# DDS_Tone_Shield.net
KiCad netlist of a schematic drawn in EAGLE
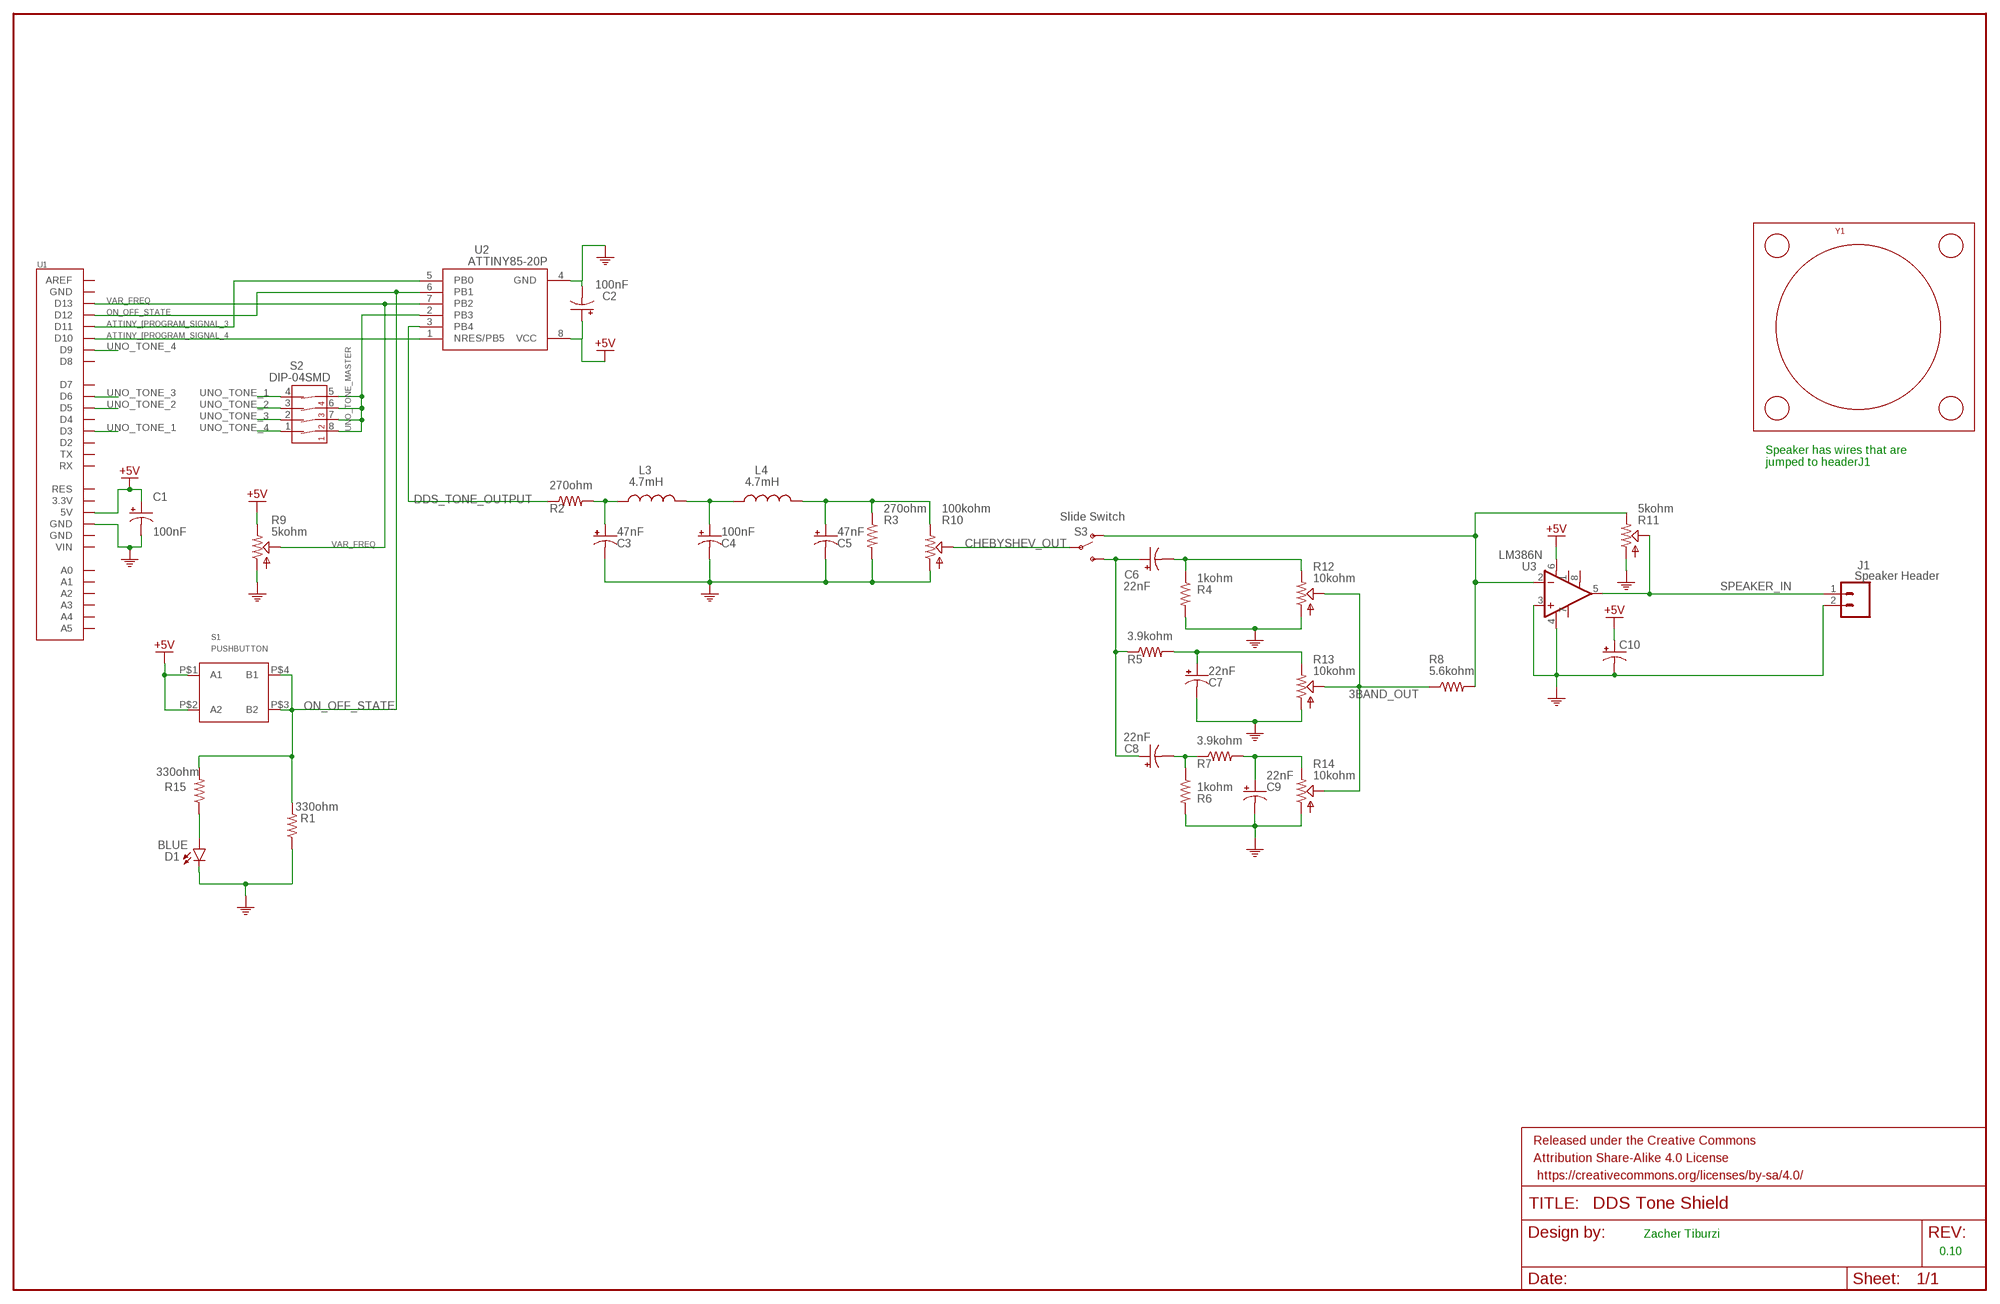
[diagram p0: schematic, sheet 1]

(export (version "E")
  (design (tool "Eeschema 10.0.6"))
  (components
    (comp (ref "C1")
      (value "100nF")
      (footprint "eagle-import:EIA3216")
      (libsource (lib "eagle-import") (part "CAP_POL1206"))
    )
    (comp (ref "C2")
      (value "100nF")
      (footprint "eagle-import:EIA3216")
      (libsource (lib "eagle-import") (part "CAP_POL1206"))
    )
    (comp (ref "C3")
      (value "47nF")
      (footprint "eagle-import:EIA3216")
      (libsource (lib "eagle-import") (part "CAP_POL1206"))
    )
    (comp (ref "C4")
      (value "100nF")
      (footprint "eagle-import:EIA3216")
      (libsource (lib "eagle-import") (part "CAP_POL1206"))
    )
    (comp (ref "C5")
      (value "47nF")
      (footprint "eagle-import:EIA3216")
      (libsource (lib "eagle-import") (part "CAP_POL1206"))
    )
    (comp (ref "C6")
      (value "22nF")
      (footprint "eagle-import:EIA3216")
      (libsource (lib "eagle-import") (part "CAP_POL1206"))
    )
    (comp (ref "C7")
      (value "22nF")
      (footprint "eagle-import:EIA3216")
      (libsource (lib "eagle-import") (part "CAP_POL1206"))
    )
    (comp (ref "C8")
      (value "22nF")
      (footprint "eagle-import:EIA3216")
      (libsource (lib "eagle-import") (part "CAP_POL1206"))
    )
    (comp (ref "C9")
      (value "22nF")
      (footprint "eagle-import:EIA3216")
      (libsource (lib "eagle-import") (part "CAP_POL1206"))
    )
    (comp (ref "C10")
      (value "CAP_POL1206")
      (footprint "eagle-import:EIA3216")
      (libsource (lib "eagle-import") (part "CAP_POL1206"))
    )
    (comp (ref "D1")
      (value "BLUE")
      (footprint "eagle-import:LED-1206")
      (libsource (lib "eagle-import") (part "LED-BLUE1206"))
    )
    (comp (ref "FRAME2")
      (value "FRAME-LEDGER")
      (footprint "eagle-import:CREATIVE_COMMONS")
      (libsource (lib "eagle-import") (part "FRAME-LEDGER"))
    )
    (comp (ref "J1")
      (value "Speaker Header")
      (footprint "eagle-import:1X02")
      (libsource (lib "eagle-import") (part "CONN_02"))
    )
    (comp (ref "L3")
      (value "4.7mH")
      (footprint "eagle-import:SDR0503-472JL")
      (libsource (lib "eagle-import") (part "INDUCTOR_"))
    )
    (comp (ref "L4")
      (value "4.7mH")
      (footprint "eagle-import:SDR0503-472JL")
      (libsource (lib "eagle-import") (part "INDUCTOR_"))
    )
    (comp (ref "R1")
      (value "330ohm")
      (footprint "eagle-import:1206")
      (libsource (lib "eagle-import") (part "RESISTOR1206"))
    )
    (comp (ref "R2")
      (value "270ohm")
      (footprint "eagle-import:1206")
      (libsource (lib "eagle-import") (part "RESISTOR1206"))
    )
    (comp (ref "R3")
      (value "270ohm")
      (footprint "eagle-import:1206")
      (libsource (lib "eagle-import") (part "RESISTOR1206"))
    )
    (comp (ref "R4")
      (value "1kohm")
      (footprint "eagle-import:1206")
      (libsource (lib "eagle-import") (part "RESISTOR1206"))
    )
    (comp (ref "R5")
      (value "3.9kohm")
      (footprint "eagle-import:1206")
      (libsource (lib "eagle-import") (part "RESISTOR1206"))
    )
    (comp (ref "R6")
      (value "1kohm")
      (footprint "eagle-import:1206")
      (libsource (lib "eagle-import") (part "RESISTOR1206"))
    )
    (comp (ref "R7")
      (value "3.9kohm")
      (footprint "eagle-import:1206")
      (libsource (lib "eagle-import") (part "RESISTOR1206"))
    )
    (comp (ref "R8")
      (value "5.6kohm")
      (footprint "eagle-import:1206")
      (libsource (lib "eagle-import") (part "RESISTOR1206"))
    )
    (comp (ref "R9")
      (value "5kohm")
      (footprint "eagle-import:RK09K_RK09D_SERIES")
      (libsource (lib "eagle-import") (part "POT1"))
    )
    (comp (ref "R10")
      (value "100kohm")
      (footprint "eagle-import:5150500311")
      (libsource (lib "eagle-import") (part "POT2"))
    )
    (comp (ref "R11")
      (value "5kohm")
      (footprint "eagle-import:RK09K_RK09D_SERIES")
      (libsource (lib "eagle-import") (part "POT1"))
    )
    (comp (ref "R12")
      (value "10kohm")
      (footprint "eagle-import:RK09K_RK09D_SERIES")
      (libsource (lib "eagle-import") (part "POT1"))
    )
    (comp (ref "R13")
      (value "10kohm")
      (footprint "eagle-import:RK09K_RK09D_SERIES")
      (libsource (lib "eagle-import") (part "POT1"))
    )
    (comp (ref "R14")
      (value "10kohm")
      (footprint "eagle-import:RK09K_RK09D_SERIES")
      (libsource (lib "eagle-import") (part "POT1"))
    )
    (comp (ref "R15")
      (value "330ohm")
      (footprint "eagle-import:1206")
      (libsource (lib "eagle-import") (part "RESISTOR1206"))
    )
    (comp (ref "S1")
      (value "PUSHBUTTON")
      (footprint "eagle-import:3CSH9_MEC_PUSHBUTTON")
      (libsource (lib "eagle-import") (part "PUSHBUTTON"))
    )
    (comp (ref "S2")
      (value "DIP-04SMD")
      (footprint "eagle-import:DIPSWITCH-04-SMD")
      (libsource (lib "eagle-import") (part "DIP-04SMD"))
    )
    (comp (ref "S3")
      (value "Slide Switch")
      (footprint "eagle-import:JS102011SAQN")
      (libsource (lib "eagle-import") (part "SWITCH-SPDT"))
    )
    (comp (ref "U1")
      (value "ARDUINO_SHIELD")
      (footprint "eagle-import:DUEMILANOVE_SHIELD")
      (libsource (lib "eagle-import") (part "ARDUINO_SHIELD"))
    )
    (comp (ref "U2")
      (value "ATTINY85-20P")
      (footprint "eagle-import:PDIP08_300MIL")
      (libsource (lib "eagle-import") (part "ATTINY85P-20"))
    )
    (comp (ref "U3")
      (value "LM386N")
      (footprint "eagle-import:DIP08")
      (libsource (lib "eagle-import") (part "LM386"))
    )
    (comp (ref "Y1")
      (value "SPEAKER")
      (footprint "eagle-import:CSS-40408N")
      (libsource (lib "eagle-import") (part "SPEAKER"))
    )
  )
  (nets
    (net (code "1") (name "+5V") (class "Default")
      (node (ref "C1") (pin "A") (pinfunction "+_A") (pintype "passive"))
      (node (ref "C10") (pin "A") (pinfunction "+_A") (pintype "passive"))
      (node (ref "C2") (pin "A") (pinfunction "+_A") (pintype "passive"))
      (node (ref "R9") (pin "P$3") (pinfunction "E_P$3") (pintype "passive"))
      (node (ref "S1") (pin "P$1") (pinfunction "A1_P$1") (pintype "bidirectional"))
      (node (ref "S1") (pin "P$2") (pinfunction "A2_P$2") (pintype "bidirectional"))
      (node (ref "U1") (pin "5V") (pinfunction "5V_5V") (pintype "bidirectional"))
      (node (ref "U2") (pin "8") (pinfunction "VCC_8") (pintype "power_in"))
      (node (ref "U3") (pin "6") (pinfunction "V+_6") (pintype "power_in"))
    )
    (net (code "2") (name "/3BAND_OUT") (class "Default")
      (node (ref "R12") (pin "P$2") (pinfunction "S_P$2") (pintype "passive"))
      (node (ref "R13") (pin "P$2") (pinfunction "S_P$2") (pintype "passive"))
      (node (ref "R14") (pin "P$2") (pinfunction "S_P$2") (pintype "passive"))
      (node (ref "R8") (pin "1") (pinfunction "1_1") (pintype "passive"))
    )
    (net (code "3") (name "/ATTINY_[PROGRAM_SIGNAL_3") (class "Default")
      (node (ref "U1") (pin "D11") (pinfunction "D11_D11") (pintype "bidirectional"))
      (node (ref "U2") (pin "5") (pinfunction "PB0_5") (pintype "bidirectional"))
    )
    (net (code "4") (name "/ATTINY_[PROGRAM_SIGNAL_4") (class "Default")
      (node (ref "U1") (pin "D10") (pinfunction "D10_D10") (pintype "bidirectional"))
      (node (ref "U2") (pin "1") (pinfunction "NRES/PB5_1") (pintype "bidirectional"))
    )
    (net (code "5") (name "/CHEBYSHEV_OUT") (class "Default")
      (node (ref "R10") (pin "P$20") (pinfunction "S_P$20") (pintype "passive"))
      (node (ref "S3") (pin "P$3") (pinfunction "P_P$3") (pintype "passive"))
    )
    (net (code "6") (name "/DDS_TONE_OUTPUT") (class "Default")
      (node (ref "R2") (pin "1") (pinfunction "1_1") (pintype "passive"))
      (node (ref "U2") (pin "3") (pinfunction "PB4_3") (pintype "bidirectional"))
    )
    (net (code "7") (name "/ON_OFF_STATE") (class "Default")
      (node (ref "R1") (pin "2") (pinfunction "2_2") (pintype "passive"))
      (node (ref "R15") (pin "2") (pinfunction "2_2") (pintype "passive"))
      (node (ref "S1") (pin "P$3") (pinfunction "B2_P$3") (pintype "bidirectional"))
      (node (ref "S1") (pin "P$4") (pinfunction "B1_P$4") (pintype "bidirectional"))
      (node (ref "U1") (pin "D12") (pinfunction "D12_D12") (pintype "bidirectional"))
      (node (ref "U2") (pin "6") (pinfunction "PB1_6") (pintype "bidirectional"))
    )
    (net (code "8") (name "/SPEAKER_IN") (class "Default")
      (node (ref "J1") (pin "1") (pinfunction "1_1") (pintype "passive"))
      (node (ref "R11") (pin "P$2") (pinfunction "S_P$2") (pintype "passive"))
      (node (ref "U3") (pin "5") (pinfunction "OUT_5") (pintype "output"))
    )
    (net (code "9") (name "/UNO_TONE_1") (class "Default")
      (node (ref "S2") (pin "4") (pinfunction "4A_4") (pintype "bidirectional"))
      (node (ref "U1") (pin "D3") (pinfunction "D3_D3") (pintype "bidirectional"))
    )
    (net (code "10") (name "/UNO_TONE_2") (class "Default")
      (node (ref "S2") (pin "3") (pinfunction "3A_3") (pintype "bidirectional"))
      (node (ref "U1") (pin "D5") (pinfunction "D5_D5") (pintype "bidirectional"))
    )
    (net (code "11") (name "/UNO_TONE_3") (class "Default")
      (node (ref "S2") (pin "2") (pinfunction "2A_2") (pintype "bidirectional"))
      (node (ref "U1") (pin "D6") (pinfunction "D6_D6") (pintype "bidirectional"))
    )
    (net (code "12") (name "/UNO_TONE_4") (class "Default")
      (node (ref "S2") (pin "1") (pinfunction "1A_1") (pintype "bidirectional"))
      (node (ref "U1") (pin "D9") (pinfunction "D9_D9") (pintype "bidirectional"))
    )
    (net (code "13") (name "/UNO_TONE_MASTER") (class "Default")
      (node (ref "S2") (pin "5") (pinfunction "4B_5") (pintype "bidirectional"))
      (node (ref "S2") (pin "6") (pinfunction "3B_6") (pintype "bidirectional"))
      (node (ref "S2") (pin "7") (pinfunction "2B_7") (pintype "bidirectional"))
      (node (ref "S2") (pin "8") (pinfunction "1B_8") (pintype "bidirectional"))
      (node (ref "U2") (pin "2") (pinfunction "PB3_2") (pintype "bidirectional"))
    )
    (net (code "14") (name "/VAR_FREQ") (class "Default")
      (node (ref "R9") (pin "P$2") (pinfunction "S_P$2") (pintype "passive"))
      (node (ref "U1") (pin "D13") (pinfunction "D13_D13") (pintype "bidirectional"))
      (node (ref "U2") (pin "7") (pinfunction "PB2_7") (pintype "bidirectional"))
    )
    (net (code "15") (name "GND_US") (class "Default")
      (node (ref "C1") (pin "C") (pinfunction "-_C") (pintype "passive"))
      (node (ref "C10") (pin "C") (pinfunction "-_C") (pintype "passive"))
      (node (ref "C2") (pin "C") (pinfunction "-_C") (pintype "passive"))
      (node (ref "C3") (pin "C") (pinfunction "-_C") (pintype "passive"))
      (node (ref "C4") (pin "C") (pinfunction "-_C") (pintype "passive"))
      (node (ref "C5") (pin "C") (pinfunction "-_C") (pintype "passive"))
      (node (ref "C7") (pin "C") (pinfunction "-_C") (pintype "passive"))
      (node (ref "C9") (pin "C") (pinfunction "-_C") (pintype "passive"))
      (node (ref "D1") (pin "C") (pinfunction "C_C") (pintype "passive"))
      (node (ref "J1") (pin "2") (pinfunction "2_2") (pintype "passive"))
      (node (ref "R1") (pin "1") (pinfunction "1_1") (pintype "passive"))
      (node (ref "R10") (pin "P$10") (pinfunction "A_P$10") (pintype "passive"))
      (node (ref "R11") (pin "P$1") (pinfunction "A_P$1") (pintype "passive"))
      (node (ref "R12") (pin "P$1") (pinfunction "A_P$1") (pintype "passive"))
      (node (ref "R13") (pin "P$1") (pinfunction "A_P$1") (pintype "passive"))
      (node (ref "R14") (pin "P$1") (pinfunction "A_P$1") (pintype "passive"))
      (node (ref "R3") (pin "2") (pinfunction "2_2") (pintype "passive"))
      (node (ref "R4") (pin "2") (pinfunction "2_2") (pintype "passive"))
      (node (ref "R6") (pin "2") (pinfunction "2_2") (pintype "passive"))
      (node (ref "R9") (pin "P$1") (pinfunction "A_P$1") (pintype "passive"))
      (node (ref "U1") (pin "GND@1") (pinfunction "GND_GND@1") (pintype "bidirectional"))
      (node (ref "U2") (pin "4") (pinfunction "GND_4") (pintype "power_in"))
      (node (ref "U3") (pin "3") (pinfunction "+IN_3") (pintype "input"))
      (node (ref "U3") (pin "4") (pinfunction "V-_4") (pintype "power_in"))
    )
    (net (code "16") (name "Net-(C3-+)") (class "Default")
      (node (ref "C3") (pin "A") (pinfunction "+_A") (pintype "passive"))
      (node (ref "L3") (pin "P$1") (pinfunction "1_P$1") (pintype "passive"))
      (node (ref "R2") (pin "2") (pinfunction "2_2") (pintype "passive"))
    )
    (net (code "17") (name "Net-(C4-+)") (class "Default")
      (node (ref "C4") (pin "A") (pinfunction "+_A") (pintype "passive"))
      (node (ref "L3") (pin "P$2") (pinfunction "2_P$2") (pintype "passive"))
      (node (ref "L4") (pin "P$1") (pinfunction "1_P$1") (pintype "passive"))
    )
    (net (code "18") (name "Net-(C5-+)") (class "Default")
      (node (ref "C5") (pin "A") (pinfunction "+_A") (pintype "passive"))
      (node (ref "L4") (pin "P$2") (pinfunction "2_P$2") (pintype "passive"))
      (node (ref "R10") (pin "P$30") (pinfunction "E_P$30") (pintype "passive"))
      (node (ref "R3") (pin "1") (pinfunction "1_1") (pintype "passive"))
    )
    (net (code "19") (name "Net-(C6-+)") (class "Default")
      (node (ref "C6") (pin "A") (pinfunction "+_A") (pintype "passive"))
      (node (ref "C8") (pin "A") (pinfunction "+_A") (pintype "passive"))
      (node (ref "R5") (pin "1") (pinfunction "1_1") (pintype "passive"))
      (node (ref "S3") (pin "P$1") (pinfunction "S_P$1") (pintype "passive"))
    )
    (net (code "20") (name "Net-(C6--)") (class "Default")
      (node (ref "C6") (pin "C") (pinfunction "-_C") (pintype "passive"))
      (node (ref "R12") (pin "P$3") (pinfunction "E_P$3") (pintype "passive"))
      (node (ref "R4") (pin "1") (pinfunction "1_1") (pintype "passive"))
    )
    (net (code "21") (name "Net-(C7-+)") (class "Default")
      (node (ref "C7") (pin "A") (pinfunction "+_A") (pintype "passive"))
      (node (ref "R13") (pin "P$3") (pinfunction "E_P$3") (pintype "passive"))
      (node (ref "R5") (pin "2") (pinfunction "2_2") (pintype "passive"))
    )
    (net (code "22") (name "Net-(C8--)") (class "Default")
      (node (ref "C8") (pin "C") (pinfunction "-_C") (pintype "passive"))
      (node (ref "R6") (pin "1") (pinfunction "1_1") (pintype "passive"))
      (node (ref "R7") (pin "1") (pinfunction "1_1") (pintype "passive"))
    )
    (net (code "23") (name "Net-(C9-+)") (class "Default")
      (node (ref "C9") (pin "A") (pinfunction "+_A") (pintype "passive"))
      (node (ref "R14") (pin "P$3") (pinfunction "E_P$3") (pintype "passive"))
      (node (ref "R7") (pin "2") (pinfunction "2_2") (pintype "passive"))
    )
    (net (code "24") (name "Net-(D1-PadA)") (class "Default")
      (node (ref "D1") (pin "A") (pinfunction "A_A") (pintype "passive"))
      (node (ref "R15") (pin "1") (pinfunction "1_1") (pintype "passive"))
    )
    (net (code "25") (name "Net-(R11-E)") (class "Default")
      (node (ref "R11") (pin "P$3") (pinfunction "E_P$3") (pintype "passive"))
      (node (ref "R8") (pin "2") (pinfunction "2_2") (pintype "passive"))
      (node (ref "S3") (pin "P$2") (pinfunction "O_P$2") (pintype "passive"))
      (node (ref "U3") (pin "2") (pinfunction "-IN_2") (pintype "input"))
    )
    (net (code "26") (name "unconnected-(U1-GND-PadGND@0)") (class "Default")
      (node (ref "U1") (pin "GND@0") (pinfunction "GND_GND@0") (pintype "bidirectional"))
    )
    (net (code "27") (name "unconnected-(U1-GND-PadGND@2)") (class "Default")
      (node (ref "U1") (pin "GND@2") (pinfunction "GND_GND@2") (pintype "bidirectional"))
    )
    (net (code "28") (name "unconnected-(U1-Pad3.3V)") (class "Default")
      (node (ref "U1") (pin "3.3V") (pinfunction "3.3V_3.3V") (pintype "bidirectional"))
    )
    (net (code "29") (name "unconnected-(U1-PadA0)") (class "Default")
      (node (ref "U1") (pin "A0") (pinfunction "A0_A0") (pintype "bidirectional"))
    )
    (net (code "30") (name "unconnected-(U1-PadA1)") (class "Default")
      (node (ref "U1") (pin "A1") (pinfunction "A1_A1") (pintype "bidirectional"))
    )
    (net (code "31") (name "unconnected-(U1-PadA2)") (class "Default")
      (node (ref "U1") (pin "A2") (pinfunction "A2_A2") (pintype "bidirectional"))
    )
    (net (code "32") (name "unconnected-(U1-PadA3)") (class "Default")
      (node (ref "U1") (pin "A3") (pinfunction "A3_A3") (pintype "bidirectional"))
    )
    (net (code "33") (name "unconnected-(U1-PadA4)") (class "Default")
      (node (ref "U1") (pin "A4") (pinfunction "A4_A4") (pintype "bidirectional"))
    )
    (net (code "34") (name "unconnected-(U1-PadA5)") (class "Default")
      (node (ref "U1") (pin "A5") (pinfunction "A5_A5") (pintype "bidirectional"))
    )
    (net (code "35") (name "unconnected-(U1-PadAREF)") (class "Default")
      (node (ref "U1") (pin "AREF") (pinfunction "AREF_AREF") (pintype "bidirectional"))
    )
    (net (code "36") (name "unconnected-(U1-PadD2)") (class "Default")
      (node (ref "U1") (pin "D2") (pinfunction "D2_D2") (pintype "bidirectional"))
    )
    (net (code "37") (name "unconnected-(U1-PadD4)") (class "Default")
      (node (ref "U1") (pin "D4") (pinfunction "D4_D4") (pintype "bidirectional"))
    )
    (net (code "38") (name "unconnected-(U1-PadD7)") (class "Default")
      (node (ref "U1") (pin "D7") (pinfunction "D7_D7") (pintype "bidirectional"))
    )
    (net (code "39") (name "unconnected-(U1-PadD8)") (class "Default")
      (node (ref "U1") (pin "D8") (pinfunction "D8_D8") (pintype "bidirectional"))
    )
    (net (code "40") (name "unconnected-(U1-PadRES)") (class "Default")
      (node (ref "U1") (pin "RES") (pinfunction "RES_RES") (pintype "bidirectional"))
    )
    (net (code "41") (name "unconnected-(U1-PadRX)") (class "Default")
      (node (ref "U1") (pin "RX") (pinfunction "RX_RX") (pintype "bidirectional"))
    )
    (net (code "42") (name "unconnected-(U1-PadTX)") (class "Default")
      (node (ref "U1") (pin "TX") (pinfunction "TX_TX") (pintype "bidirectional"))
    )
    (net (code "43") (name "unconnected-(U1-PadVIN)") (class "Default")
      (node (ref "U1") (pin "VIN") (pinfunction "VIN_VIN") (pintype "bidirectional"))
    )
    (net (code "44") (name "unconnected-(U3-BP-Pad7)") (class "Default")
      (node (ref "U3") (pin "7") (pinfunction "BP_7") (pintype "bidirectional"))
    )
    (net (code "45") (name "unconnected-(U3-GAIN-Pad1)") (class "Default")
      (node (ref "U3") (pin "1") (pinfunction "GAIN_1") (pintype "bidirectional"))
    )
    (net (code "46") (name "unconnected-(U3-GAIN-Pad8)") (class "Default")
      (node (ref "U3") (pin "8") (pinfunction "GAIN_8") (pintype "bidirectional"))
    )
  )
)
